# 5_cpu_alu.net
KiCad netlist of a schematic drawn in EAGLE
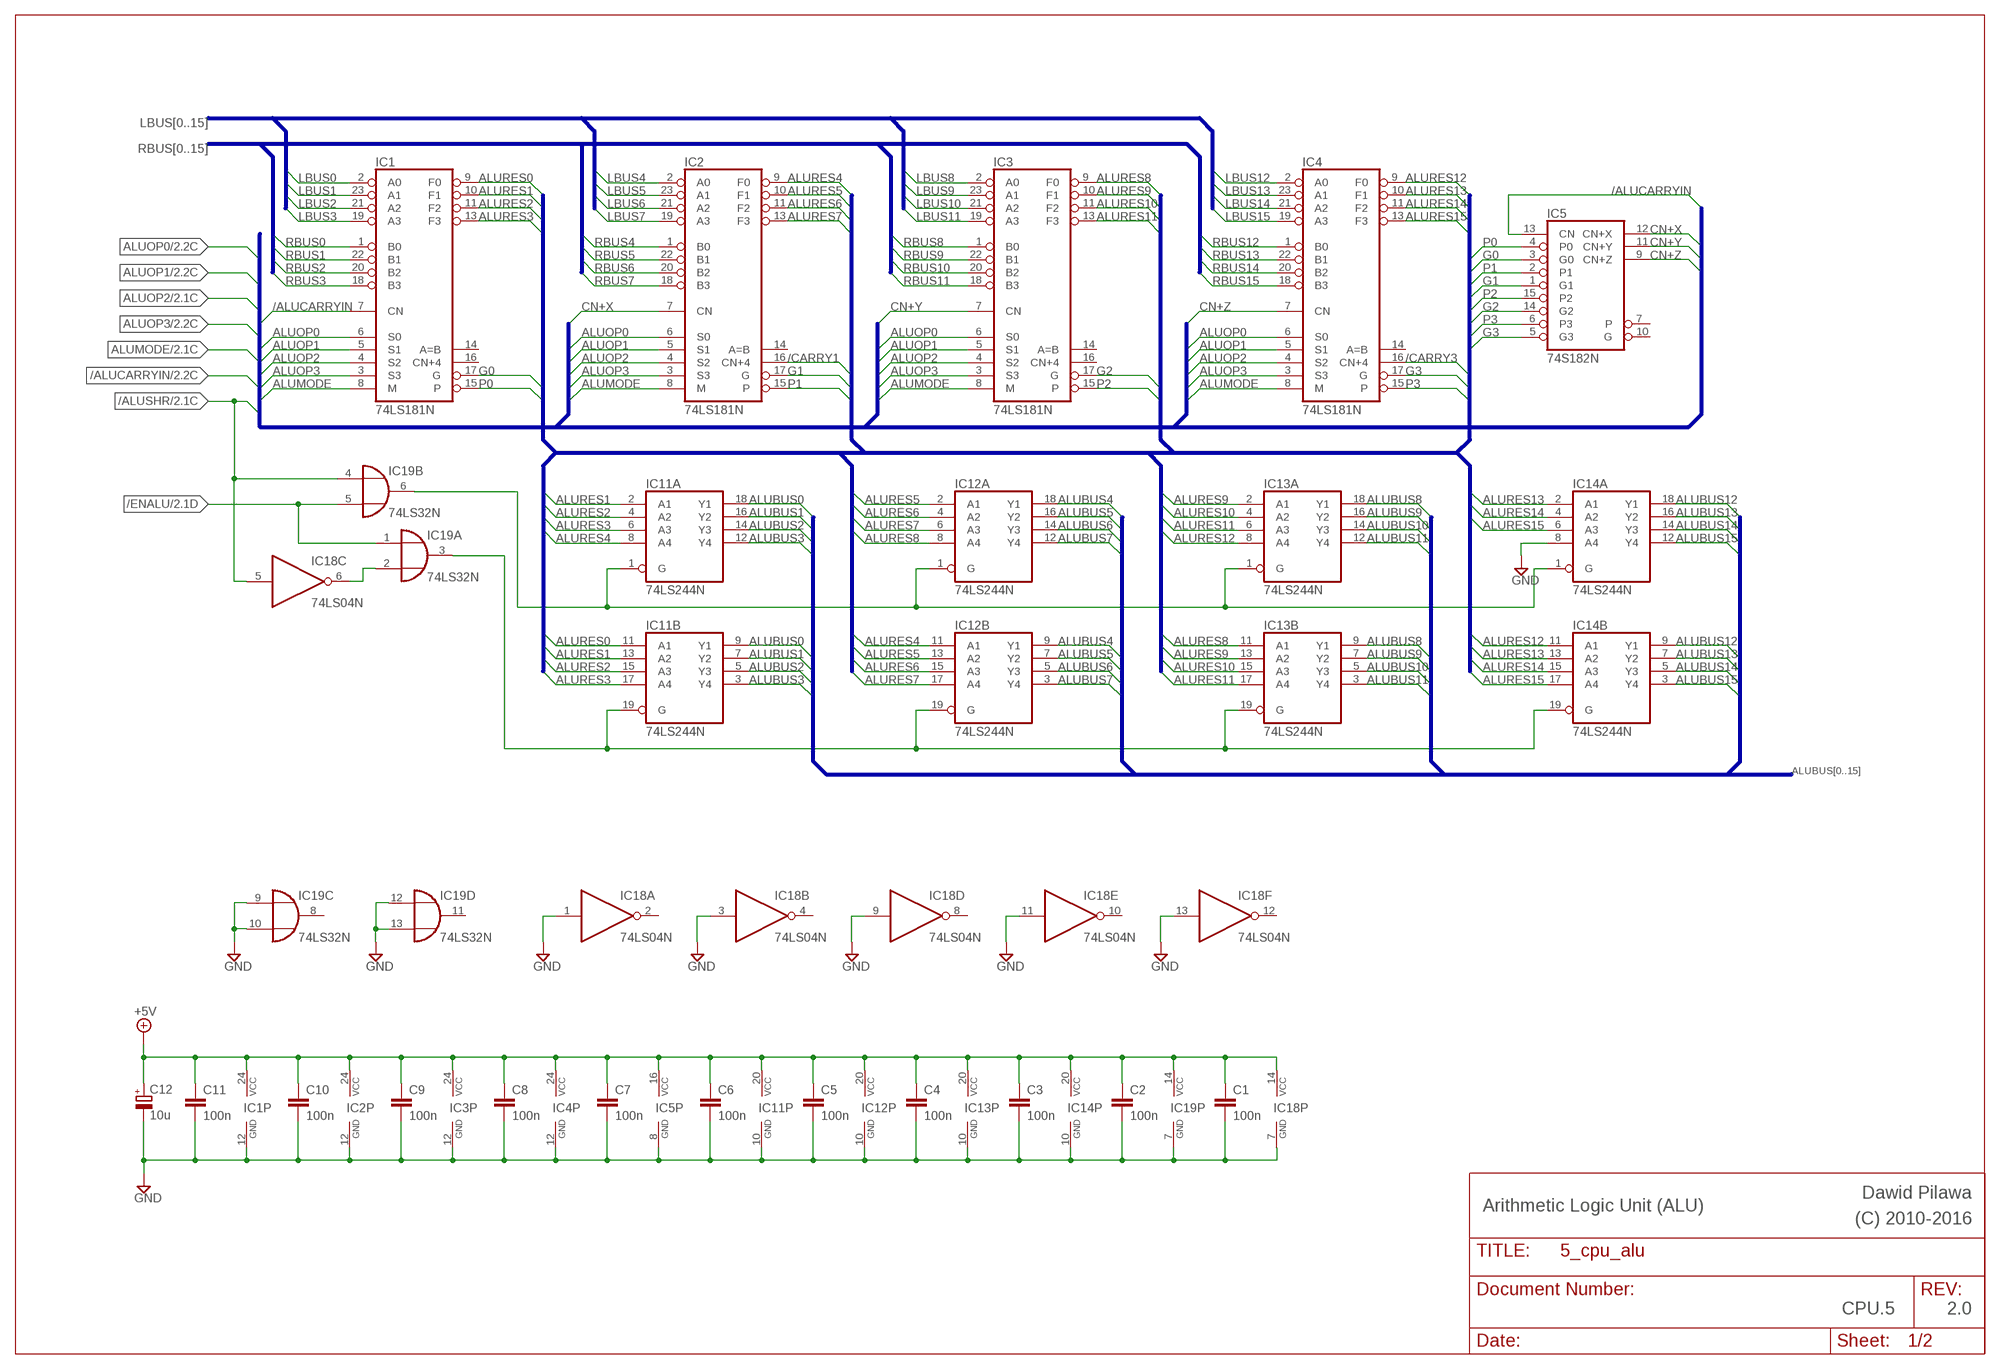
[diagram p0: schematic, sheet 1]
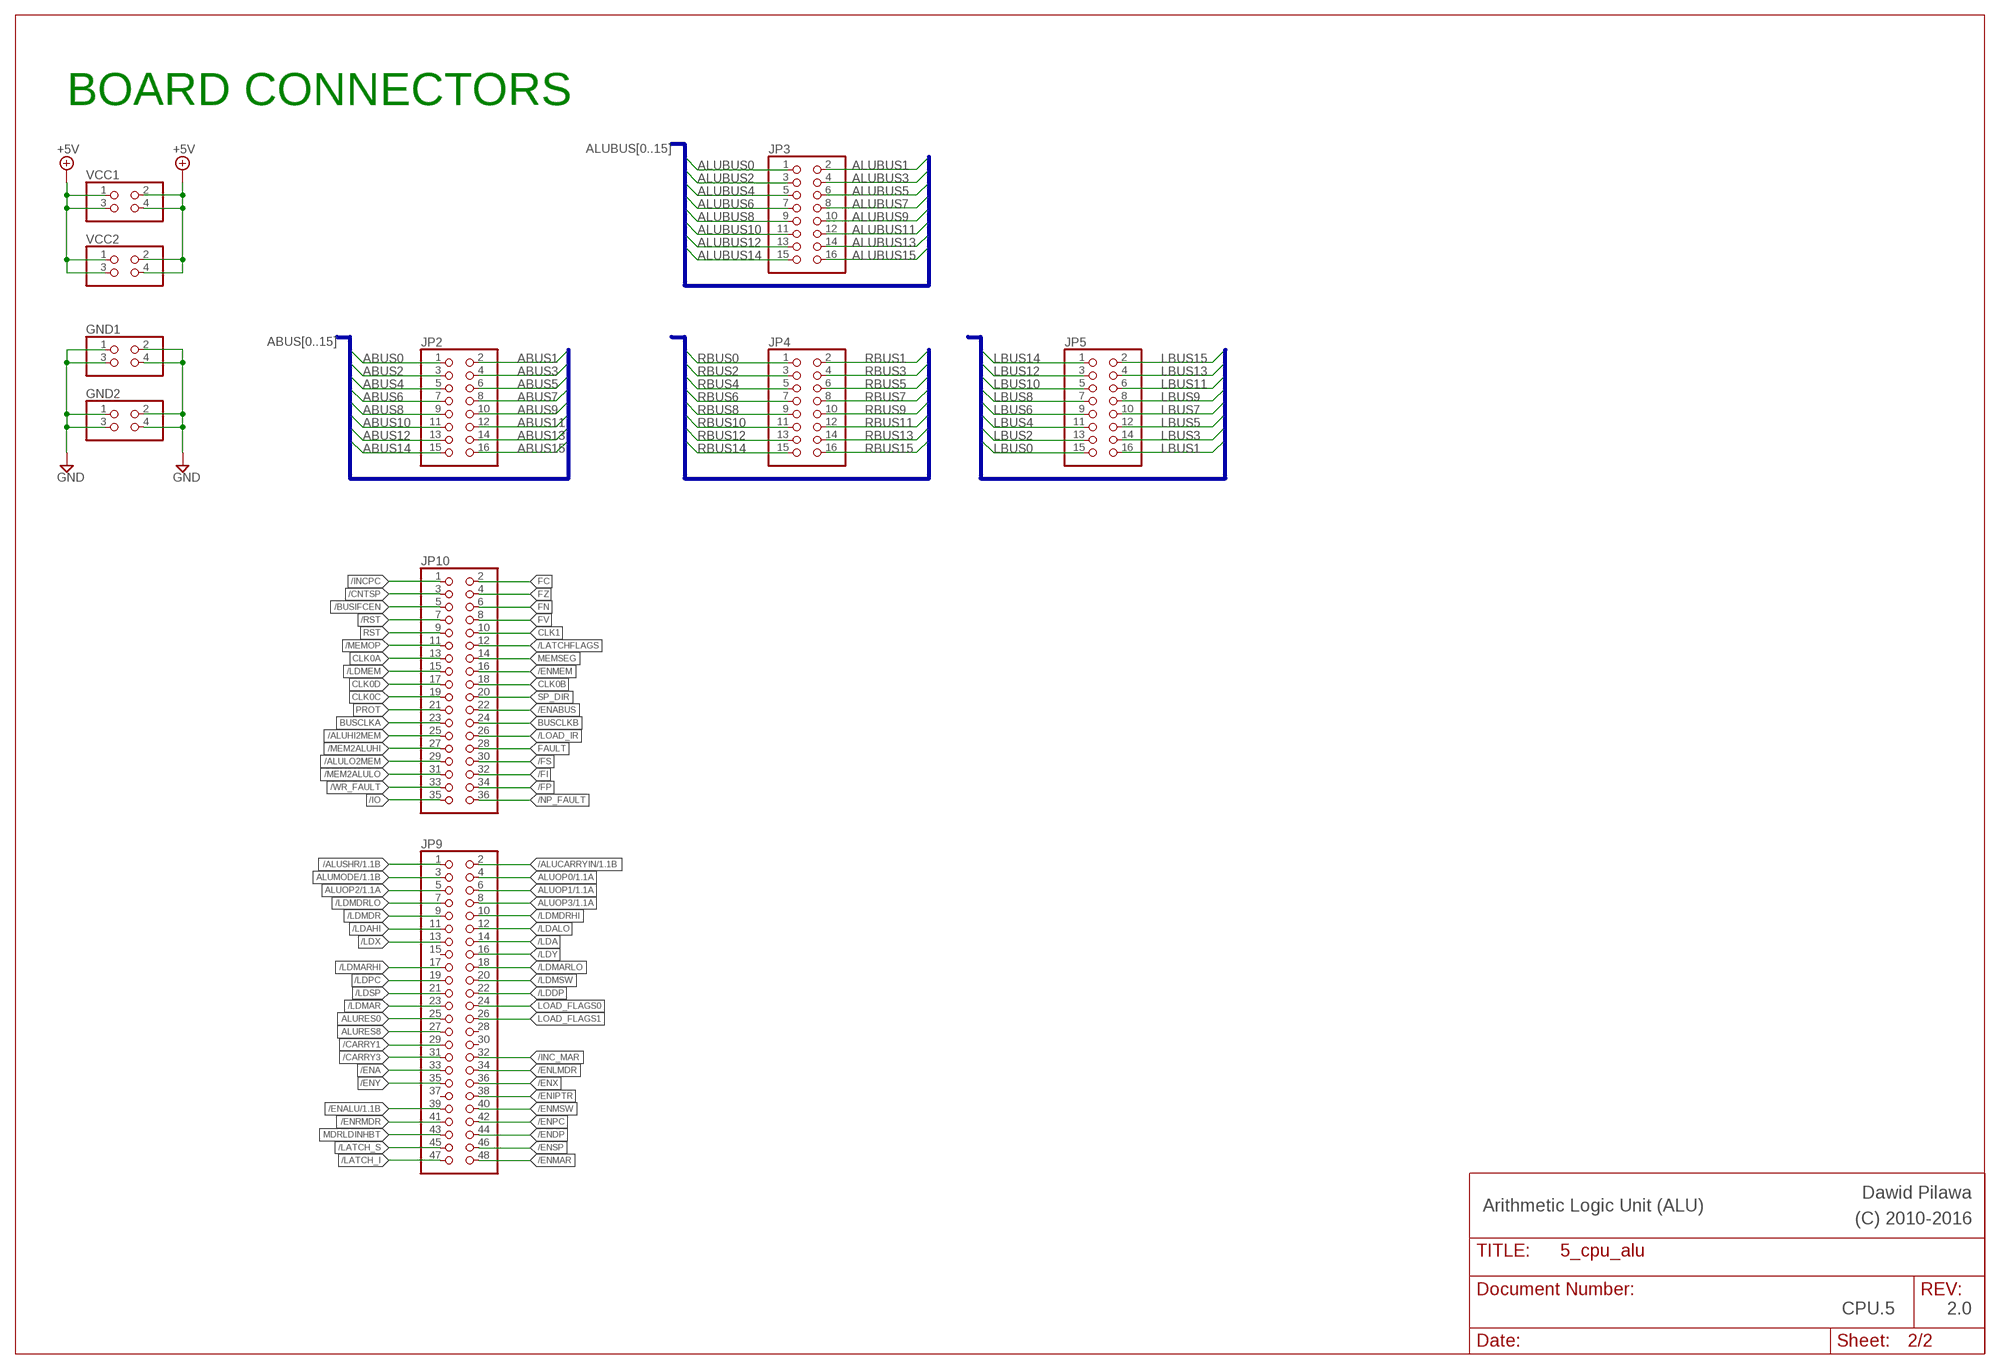
[diagram p1: schematic, sheet 2]

(export (version "E")
  (design (tool "Eeschema 10.0.6"))
  (components
    (comp (ref "C1")
      (value "100n")
      (footprint "eagle-import:C050-024X044")
      (libsource (lib "eagle-import") (part "C-EU050-024X044"))
    )
    (comp (ref "C2")
      (value "100n")
      (footprint "eagle-import:C050-024X044")
      (libsource (lib "eagle-import") (part "C-EU050-024X044"))
    )
    (comp (ref "C3")
      (value "100n")
      (footprint "eagle-import:C050-024X044")
      (libsource (lib "eagle-import") (part "C-EU050-024X044"))
    )
    (comp (ref "C4")
      (value "100n")
      (footprint "eagle-import:C050-024X044")
      (libsource (lib "eagle-import") (part "C-EU050-024X044"))
    )
    (comp (ref "C5")
      (value "100n")
      (footprint "eagle-import:C050-024X044")
      (libsource (lib "eagle-import") (part "C-EU050-024X044"))
    )
    (comp (ref "C6")
      (value "100n")
      (footprint "eagle-import:C050-024X044")
      (libsource (lib "eagle-import") (part "C-EU050-024X044"))
    )
    (comp (ref "C7")
      (value "100n")
      (footprint "eagle-import:C050-024X044")
      (libsource (lib "eagle-import") (part "C-EU050-024X044"))
    )
    (comp (ref "C8")
      (value "100n")
      (footprint "eagle-import:C050-024X044")
      (libsource (lib "eagle-import") (part "C-EU050-024X044"))
    )
    (comp (ref "C9")
      (value "100n")
      (footprint "eagle-import:C050-024X044")
      (libsource (lib "eagle-import") (part "C-EU050-024X044"))
    )
    (comp (ref "C10")
      (value "100n")
      (footprint "eagle-import:C050-024X044")
      (libsource (lib "eagle-import") (part "C-EU050-024X044"))
    )
    (comp (ref "C11")
      (value "100n")
      (footprint "eagle-import:C050-024X044")
      (libsource (lib "eagle-import") (part "C-EU050-024X044"))
    )
    (comp (ref "C12")
      (value "10u")
      (footprint "eagle-import:E2,5-6")
      (libsource (lib "eagle-import") (part "CPOL-EUE2.5-6"))
    )
    (comp (ref "IC1")
      (value "74LS181N")
      (footprint "eagle-import:DIL24-6")
      (libsource (lib "eagle-import") (part "74181NLS"))
    )
    (comp (ref "IC2")
      (value "74LS181N")
      (footprint "eagle-import:DIL24-6")
      (libsource (lib "eagle-import") (part "74181NLS"))
    )
    (comp (ref "IC3")
      (value "74LS181N")
      (footprint "eagle-import:DIL24-6")
      (libsource (lib "eagle-import") (part "74181NLS"))
    )
    (comp (ref "IC4")
      (value "74LS181N")
      (footprint "eagle-import:DIL24-6")
      (libsource (lib "eagle-import") (part "74181NLS"))
    )
    (comp (ref "IC5")
      (value "74S182N")
      (footprint "eagle-import:DIL16")
      (libsource (lib "eagle-import") (part "74182NS"))
    )
    (comp (ref "IC11")
      (value "74LS244N")
      (footprint "eagle-import:DIL20")
      (libsource (lib "eagle-import") (part "74244NLS"))
    )
    (comp (ref "IC12")
      (value "74LS244N")
      (footprint "eagle-import:DIL20")
      (libsource (lib "eagle-import") (part "74244NLS"))
    )
    (comp (ref "IC13")
      (value "74LS244N")
      (footprint "eagle-import:DIL20")
      (libsource (lib "eagle-import") (part "74244NLS"))
    )
    (comp (ref "IC14")
      (value "74LS244N")
      (footprint "eagle-import:DIL20")
      (libsource (lib "eagle-import") (part "74244NLS"))
    )
    (comp (ref "IC18")
      (value "74LS04N")
      (footprint "eagle-import:DIL14")
      (libsource (lib "eagle-import") (part "7404NLS"))
    )
    (comp (ref "IC19")
      (value "74LS32N")
      (footprint "eagle-import:DIL14")
      (libsource (lib "eagle-import") (part "7432NLS"))
    )
    (comp (ref "GND1")
      (value "PINHD-2X2")
      (footprint "eagle-import:2X02")
      (libsource (lib "eagle-import") (part "PINHD-2X2"))
    )
    (comp (ref "GND2")
      (value "PINHD-2X2")
      (footprint "eagle-import:2X02")
      (libsource (lib "eagle-import") (part "PINHD-2X2"))
    )
    (comp (ref "JP2")
      (value "PINHD-2X8")
      (footprint "eagle-import:2X08")
      (libsource (lib "eagle-import") (part "PINHD-2X8"))
    )
    (comp (ref "JP3")
      (value "PINHD-2X8")
      (footprint "eagle-import:2X08")
      (libsource (lib "eagle-import") (part "PINHD-2X8"))
    )
    (comp (ref "JP4")
      (value "PINHD-2X8")
      (footprint "eagle-import:2X08")
      (libsource (lib "eagle-import") (part "PINHD-2X8"))
    )
    (comp (ref "JP5")
      (value "PINHD-2X8")
      (footprint "eagle-import:2X08")
      (libsource (lib "eagle-import") (part "PINHD-2X8"))
    )
    (comp (ref "JP9")
      (value "PINHD-2X24")
      (footprint "eagle-import:2X24")
      (libsource (lib "eagle-import") (part "PINHD-2X24"))
    )
    (comp (ref "JP10")
      (value "PINHD-2X18")
      (footprint "eagle-import:2X18")
      (libsource (lib "eagle-import") (part "PINHD-2X18"))
    )
    (comp (ref "VCC1")
      (value "PINHD-2X2")
      (footprint "eagle-import:2X02")
      (libsource (lib "eagle-import") (part "PINHD-2X2"))
    )
    (comp (ref "VCC2")
      (value "PINHD-2X2")
      (footprint "eagle-import:2X02")
      (libsource (lib "eagle-import") (part "PINHD-2X2"))
    )
  )
  (nets
    (net (code "1") (name "+5V") (class "Default")
      (node (ref "C1") (pin "1") (pinfunction "1_1") (pintype "passive"))
      (node (ref "C10") (pin "1") (pinfunction "1_1") (pintype "passive"))
      (node (ref "C11") (pin "1") (pinfunction "1_1") (pintype "passive"))
      (node (ref "C12") (pin "+") (pinfunction "+_+") (pintype "passive"))
      (node (ref "C2") (pin "1") (pinfunction "1_1") (pintype "passive"))
      (node (ref "C3") (pin "1") (pinfunction "1_1") (pintype "passive"))
      (node (ref "C4") (pin "1") (pinfunction "1_1") (pintype "passive"))
      (node (ref "C5") (pin "1") (pinfunction "1_1") (pintype "passive"))
      (node (ref "C6") (pin "1") (pinfunction "1_1") (pintype "passive"))
      (node (ref "C7") (pin "1") (pinfunction "1_1") (pintype "passive"))
      (node (ref "C8") (pin "1") (pinfunction "1_1") (pintype "passive"))
      (node (ref "C9") (pin "1") (pinfunction "1_1") (pintype "passive"))
      (node (ref "IC1") (pin "24") (pinfunction "VCC_24") (pintype "power_in"))
      (node (ref "IC11") (pin "20") (pinfunction "VCC_20") (pintype "power_in"))
      (node (ref "IC12") (pin "20") (pinfunction "VCC_20") (pintype "power_in"))
      (node (ref "IC13") (pin "20") (pinfunction "VCC_20") (pintype "power_in"))
      (node (ref "IC14") (pin "20") (pinfunction "VCC_20") (pintype "power_in"))
      (node (ref "IC18") (pin "14") (pinfunction "VCC_14") (pintype "power_in"))
      (node (ref "IC19") (pin "14") (pinfunction "VCC_14") (pintype "power_in"))
      (node (ref "IC2") (pin "24") (pinfunction "VCC_24") (pintype "power_in"))
      (node (ref "IC3") (pin "24") (pinfunction "VCC_24") (pintype "power_in"))
      (node (ref "IC4") (pin "24") (pinfunction "VCC_24") (pintype "power_in"))
      (node (ref "IC5") (pin "16") (pinfunction "VCC_16") (pintype "power_in"))
      (node (ref "VCC1") (pin "1") (pinfunction "1_1") (pintype "passive"))
      (node (ref "VCC1") (pin "2") (pinfunction "2_2") (pintype "passive"))
      (node (ref "VCC1") (pin "3") (pinfunction "3_3") (pintype "passive"))
      (node (ref "VCC1") (pin "4") (pinfunction "4_4") (pintype "passive"))
      (node (ref "VCC2") (pin "1") (pinfunction "1_1") (pintype "passive"))
      (node (ref "VCC2") (pin "2") (pinfunction "2_2") (pintype "passive"))
      (node (ref "VCC2") (pin "3") (pinfunction "3_3") (pintype "passive"))
      (node (ref "VCC2") (pin "4") (pinfunction "4_4") (pintype "passive"))
    )
    (net (code "8") (name "ABUS0") (class "Default")
      (node (ref "JP2") (pin "1") (pinfunction "1_1") (pintype "passive"))
    )
    (net (code "9") (name "ABUS1") (class "Default")
      (node (ref "JP2") (pin "2") (pinfunction "2_2") (pintype "passive"))
    )
    (net (code "10") (name "ABUS2") (class "Default")
      (node (ref "JP2") (pin "3") (pinfunction "3_3") (pintype "passive"))
    )
    (net (code "11") (name "ABUS3") (class "Default")
      (node (ref "JP2") (pin "4") (pinfunction "4_4") (pintype "passive"))
    )
    (net (code "12") (name "ABUS4") (class "Default")
      (node (ref "JP2") (pin "5") (pinfunction "5_5") (pintype "passive"))
    )
    (net (code "13") (name "ABUS5") (class "Default")
      (node (ref "JP2") (pin "6") (pinfunction "6_6") (pintype "passive"))
    )
    (net (code "14") (name "ABUS6") (class "Default")
      (node (ref "JP2") (pin "7") (pinfunction "7_7") (pintype "passive"))
    )
    (net (code "15") (name "ABUS7") (class "Default")
      (node (ref "JP2") (pin "8") (pinfunction "8_8") (pintype "passive"))
    )
    (net (code "16") (name "ABUS8") (class "Default")
      (node (ref "JP2") (pin "9") (pinfunction "9_9") (pintype "passive"))
    )
    (net (code "17") (name "ABUS9") (class "Default")
      (node (ref "JP2") (pin "10") (pinfunction "10_10") (pintype "passive"))
    )
    (net (code "18") (name "ABUS10") (class "Default")
      (node (ref "JP2") (pin "11") (pinfunction "11_11") (pintype "passive"))
    )
    (net (code "19") (name "ABUS11") (class "Default")
      (node (ref "JP2") (pin "12") (pinfunction "12_12") (pintype "passive"))
    )
    (net (code "20") (name "ABUS12") (class "Default")
      (node (ref "JP2") (pin "13") (pinfunction "13_13") (pintype "passive"))
    )
    (net (code "21") (name "ABUS13") (class "Default")
      (node (ref "JP2") (pin "14") (pinfunction "14_14") (pintype "passive"))
    )
    (net (code "22") (name "ABUS14") (class "Default")
      (node (ref "JP2") (pin "15") (pinfunction "15_15") (pintype "passive"))
    )
    (net (code "23") (name "ABUS15") (class "Default")
      (node (ref "JP2") (pin "16") (pinfunction "16_16") (pintype "passive"))
    )
    (net (code "24") (name "ALUBUS0") (class "Default")
      (node (ref "IC11") (pin "18") (pinfunction "Y1_18") (pintype "tri_state"))
      (node (ref "IC11") (pin "9") (pinfunction "Y1_9") (pintype "tri_state"))
      (node (ref "JP3") (pin "1") (pinfunction "1_1") (pintype "passive"))
    )
    (net (code "25") (name "ALUBUS1") (class "Default")
      (node (ref "IC11") (pin "16") (pinfunction "Y2_16") (pintype "tri_state"))
      (node (ref "IC11") (pin "7") (pinfunction "Y2_7") (pintype "tri_state"))
      (node (ref "JP3") (pin "2") (pinfunction "2_2") (pintype "passive"))
    )
    (net (code "26") (name "ALUBUS2") (class "Default")
      (node (ref "IC11") (pin "14") (pinfunction "Y3_14") (pintype "tri_state"))
      (node (ref "IC11") (pin "5") (pinfunction "Y3_5") (pintype "tri_state"))
      (node (ref "JP3") (pin "3") (pinfunction "3_3") (pintype "passive"))
    )
    (net (code "27") (name "ALUBUS3") (class "Default")
      (node (ref "IC11") (pin "12") (pinfunction "Y4_12") (pintype "tri_state"))
      (node (ref "IC11") (pin "3") (pinfunction "Y4_3") (pintype "tri_state"))
      (node (ref "JP3") (pin "4") (pinfunction "4_4") (pintype "passive"))
    )
    (net (code "28") (name "ALUBUS4") (class "Default")
      (node (ref "IC12") (pin "18") (pinfunction "Y1_18") (pintype "tri_state"))
      (node (ref "IC12") (pin "9") (pinfunction "Y1_9") (pintype "tri_state"))
      (node (ref "JP3") (pin "5") (pinfunction "5_5") (pintype "passive"))
    )
    (net (code "29") (name "ALUBUS5") (class "Default")
      (node (ref "IC12") (pin "16") (pinfunction "Y2_16") (pintype "tri_state"))
      (node (ref "IC12") (pin "7") (pinfunction "Y2_7") (pintype "tri_state"))
      (node (ref "JP3") (pin "6") (pinfunction "6_6") (pintype "passive"))
    )
    (net (code "30") (name "ALUBUS6") (class "Default")
      (node (ref "IC12") (pin "14") (pinfunction "Y3_14") (pintype "tri_state"))
      (node (ref "IC12") (pin "5") (pinfunction "Y3_5") (pintype "tri_state"))
      (node (ref "JP3") (pin "7") (pinfunction "7_7") (pintype "passive"))
    )
    (net (code "31") (name "ALUBUS7") (class "Default")
      (node (ref "IC12") (pin "12") (pinfunction "Y4_12") (pintype "tri_state"))
      (node (ref "IC12") (pin "3") (pinfunction "Y4_3") (pintype "tri_state"))
      (node (ref "JP3") (pin "8") (pinfunction "8_8") (pintype "passive"))
    )
    (net (code "32") (name "ALUBUS8") (class "Default")
      (node (ref "IC13") (pin "18") (pinfunction "Y1_18") (pintype "tri_state"))
      (node (ref "IC13") (pin "9") (pinfunction "Y1_9") (pintype "tri_state"))
      (node (ref "JP3") (pin "9") (pinfunction "9_9") (pintype "passive"))
    )
    (net (code "33") (name "ALUBUS9") (class "Default")
      (node (ref "IC13") (pin "16") (pinfunction "Y2_16") (pintype "tri_state"))
      (node (ref "IC13") (pin "7") (pinfunction "Y2_7") (pintype "tri_state"))
      (node (ref "JP3") (pin "10") (pinfunction "10_10") (pintype "passive"))
    )
    (net (code "34") (name "ALUBUS10") (class "Default")
      (node (ref "IC13") (pin "14") (pinfunction "Y3_14") (pintype "tri_state"))
      (node (ref "IC13") (pin "5") (pinfunction "Y3_5") (pintype "tri_state"))
      (node (ref "JP3") (pin "11") (pinfunction "11_11") (pintype "passive"))
    )
    (net (code "35") (name "ALUBUS11") (class "Default")
      (node (ref "IC13") (pin "12") (pinfunction "Y4_12") (pintype "tri_state"))
      (node (ref "IC13") (pin "3") (pinfunction "Y4_3") (pintype "tri_state"))
      (node (ref "JP3") (pin "12") (pinfunction "12_12") (pintype "passive"))
    )
    (net (code "36") (name "ALUBUS12") (class "Default")
      (node (ref "IC14") (pin "18") (pinfunction "Y1_18") (pintype "tri_state"))
      (node (ref "IC14") (pin "9") (pinfunction "Y1_9") (pintype "tri_state"))
      (node (ref "JP3") (pin "13") (pinfunction "13_13") (pintype "passive"))
    )
    (net (code "37") (name "ALUBUS13") (class "Default")
      (node (ref "IC14") (pin "16") (pinfunction "Y2_16") (pintype "tri_state"))
      (node (ref "IC14") (pin "7") (pinfunction "Y2_7") (pintype "tri_state"))
      (node (ref "JP3") (pin "14") (pinfunction "14_14") (pintype "passive"))
    )
    (net (code "38") (name "ALUBUS14") (class "Default")
      (node (ref "IC14") (pin "14") (pinfunction "Y3_14") (pintype "tri_state"))
      (node (ref "IC14") (pin "5") (pinfunction "Y3_5") (pintype "tri_state"))
      (node (ref "JP3") (pin "15") (pinfunction "15_15") (pintype "passive"))
    )
    (net (code "39") (name "ALUBUS15") (class "Default")
      (node (ref "IC14") (pin "12") (pinfunction "Y4_12") (pintype "tri_state"))
      (node (ref "IC14") (pin "3") (pinfunction "Y4_3") (pintype "tri_state"))
      (node (ref "JP3") (pin "16") (pinfunction "16_16") (pintype "passive"))
    )
    (net (code "40") (name "ALUMODE") (class "Default")
      (node (ref "IC1") (pin "8") (pinfunction "M_8") (pintype "input"))
      (node (ref "IC2") (pin "8") (pinfunction "M_8") (pintype "input"))
      (node (ref "IC3") (pin "8") (pinfunction "M_8") (pintype "input"))
      (node (ref "IC4") (pin "8") (pinfunction "M_8") (pintype "input"))
      (node (ref "JP9") (pin "3") (pinfunction "3_3") (pintype "passive"))
    )
    (net (code "41") (name "ALUOP0") (class "Default")
      (node (ref "IC1") (pin "6") (pinfunction "S0_6") (pintype "input"))
      (node (ref "IC2") (pin "6") (pinfunction "S0_6") (pintype "input"))
      (node (ref "IC3") (pin "6") (pinfunction "S0_6") (pintype "input"))
      (node (ref "IC4") (pin "6") (pinfunction "S0_6") (pintype "input"))
      (node (ref "JP9") (pin "4") (pinfunction "4_4") (pintype "passive"))
    )
    (net (code "42") (name "ALUOP1") (class "Default")
      (node (ref "IC1") (pin "5") (pinfunction "S1_5") (pintype "input"))
      (node (ref "IC2") (pin "5") (pinfunction "S1_5") (pintype "input"))
      (node (ref "IC3") (pin "5") (pinfunction "S1_5") (pintype "input"))
      (node (ref "IC4") (pin "5") (pinfunction "S1_5") (pintype "input"))
      (node (ref "JP9") (pin "6") (pinfunction "6_6") (pintype "passive"))
    )
    (net (code "43") (name "ALUOP2") (class "Default")
      (node (ref "IC1") (pin "4") (pinfunction "S2_4") (pintype "input"))
      (node (ref "IC2") (pin "4") (pinfunction "S2_4") (pintype "input"))
      (node (ref "IC3") (pin "4") (pinfunction "S2_4") (pintype "input"))
      (node (ref "IC4") (pin "4") (pinfunction "S2_4") (pintype "input"))
      (node (ref "JP9") (pin "5") (pinfunction "5_5") (pintype "passive"))
    )
    (net (code "44") (name "ALUOP3") (class "Default")
      (node (ref "IC1") (pin "3") (pinfunction "S3_3") (pintype "input"))
      (node (ref "IC2") (pin "3") (pinfunction "S3_3") (pintype "input"))
      (node (ref "IC3") (pin "3") (pinfunction "S3_3") (pintype "input"))
      (node (ref "IC4") (pin "3") (pinfunction "S3_3") (pintype "input"))
      (node (ref "JP9") (pin "8") (pinfunction "8_8") (pintype "passive"))
    )
    (net (code "45") (name "ALURES0") (class "Default")
      (node (ref "IC1") (pin "9") (pinfunction "F0_9") (pintype "output"))
      (node (ref "IC11") (pin "11") (pinfunction "A1_11") (pintype "input"))
      (node (ref "JP9") (pin "25") (pinfunction "25_25") (pintype "passive"))
    )
    (net (code "46") (name "ALURES1") (class "Default")
      (node (ref "IC1") (pin "10") (pinfunction "F1_10") (pintype "output"))
      (node (ref "IC11") (pin "13") (pinfunction "A2_13") (pintype "input"))
      (node (ref "IC11") (pin "2") (pinfunction "A1_2") (pintype "input"))
    )
    (net (code "47") (name "ALURES2") (class "Default")
      (node (ref "IC1") (pin "11") (pinfunction "F2_11") (pintype "output"))
      (node (ref "IC11") (pin "15") (pinfunction "A3_15") (pintype "input"))
      (node (ref "IC11") (pin "4") (pinfunction "A2_4") (pintype "input"))
    )
    (net (code "48") (name "ALURES3") (class "Default")
      (node (ref "IC1") (pin "13") (pinfunction "F3_13") (pintype "output"))
      (node (ref "IC11") (pin "17") (pinfunction "A4_17") (pintype "input"))
      (node (ref "IC11") (pin "6") (pinfunction "A3_6") (pintype "input"))
    )
    (net (code "49") (name "ALURES4") (class "Default")
      (node (ref "IC11") (pin "8") (pinfunction "A4_8") (pintype "input"))
      (node (ref "IC12") (pin "11") (pinfunction "A1_11") (pintype "input"))
      (node (ref "IC2") (pin "9") (pinfunction "F0_9") (pintype "output"))
    )
    (net (code "50") (name "ALURES5") (class "Default")
      (node (ref "IC12") (pin "13") (pinfunction "A2_13") (pintype "input"))
      (node (ref "IC12") (pin "2") (pinfunction "A1_2") (pintype "input"))
      (node (ref "IC2") (pin "10") (pinfunction "F1_10") (pintype "output"))
    )
    (net (code "51") (name "ALURES6") (class "Default")
      (node (ref "IC12") (pin "15") (pinfunction "A3_15") (pintype "input"))
      (node (ref "IC12") (pin "4") (pinfunction "A2_4") (pintype "input"))
      (node (ref "IC2") (pin "11") (pinfunction "F2_11") (pintype "output"))
    )
    (net (code "52") (name "ALURES7") (class "Default")
      (node (ref "IC12") (pin "17") (pinfunction "A4_17") (pintype "input"))
      (node (ref "IC12") (pin "6") (pinfunction "A3_6") (pintype "input"))
      (node (ref "IC2") (pin "13") (pinfunction "F3_13") (pintype "output"))
    )
    (net (code "53") (name "ALURES8") (class "Default")
      (node (ref "IC12") (pin "8") (pinfunction "A4_8") (pintype "input"))
      (node (ref "IC13") (pin "11") (pinfunction "A1_11") (pintype "input"))
      (node (ref "IC3") (pin "9") (pinfunction "F0_9") (pintype "output"))
      (node (ref "JP9") (pin "27") (pinfunction "27_27") (pintype "passive"))
    )
    (net (code "54") (name "ALURES9") (class "Default")
      (node (ref "IC13") (pin "13") (pinfunction "A2_13") (pintype "input"))
      (node (ref "IC13") (pin "2") (pinfunction "A1_2") (pintype "input"))
      (node (ref "IC3") (pin "10") (pinfunction "F1_10") (pintype "output"))
    )
    (net (code "55") (name "ALURES10") (class "Default")
      (node (ref "IC13") (pin "15") (pinfunction "A3_15") (pintype "input"))
      (node (ref "IC13") (pin "4") (pinfunction "A2_4") (pintype "input"))
      (node (ref "IC3") (pin "11") (pinfunction "F2_11") (pintype "output"))
    )
    (net (code "56") (name "ALURES11") (class "Default")
      (node (ref "IC13") (pin "17") (pinfunction "A4_17") (pintype "input"))
      (node (ref "IC13") (pin "6") (pinfunction "A3_6") (pintype "input"))
      (node (ref "IC3") (pin "13") (pinfunction "F3_13") (pintype "output"))
    )
    (net (code "57") (name "ALURES12") (class "Default")
      (node (ref "IC13") (pin "8") (pinfunction "A4_8") (pintype "input"))
      (node (ref "IC14") (pin "11") (pinfunction "A1_11") (pintype "input"))
      (node (ref "IC4") (pin "9") (pinfunction "F0_9") (pintype "output"))
    )
    (net (code "58") (name "ALURES13") (class "Default")
      (node (ref "IC14") (pin "13") (pinfunction "A2_13") (pintype "input"))
      (node (ref "IC14") (pin "2") (pinfunction "A1_2") (pintype "input"))
      (node (ref "IC4") (pin "10") (pinfunction "F1_10") (pintype "output"))
    )
    (net (code "59") (name "ALURES14") (class "Default")
      (node (ref "IC14") (pin "15") (pinfunction "A3_15") (pintype "input"))
      (node (ref "IC14") (pin "4") (pinfunction "A2_4") (pintype "input"))
      (node (ref "IC4") (pin "11") (pinfunction "F2_11") (pintype "output"))
    )
    (net (code "60") (name "ALURES15") (class "Default")
      (node (ref "IC14") (pin "17") (pinfunction "A4_17") (pintype "input"))
      (node (ref "IC14") (pin "6") (pinfunction "A3_6") (pintype "input"))
      (node (ref "IC4") (pin "13") (pinfunction "F3_13") (pintype "output"))
    )
    (net (code "61") (name "BUSCLKA") (class "Default")
      (node (ref "JP10") (pin "23") (pinfunction "23_23") (pintype "passive"))
    )
    (net (code "62") (name "BUSCLKB") (class "Default")
      (node (ref "JP10") (pin "24") (pinfunction "24_24") (pintype "passive"))
    )
    (net (code "63") (name "CLK0A") (class "Default")
      (node (ref "JP10") (pin "13") (pinfunction "13_13") (pintype "passive"))
    )
    (net (code "64") (name "CLK0B") (class "Default")
      (node (ref "JP10") (pin "18") (pinfunction "18_18") (pintype "passive"))
    )
    (net (code "65") (name "CLK0C") (class "Default")
      (node (ref "JP10") (pin "19") (pinfunction "19_19") (pintype "passive"))
    )
    (net (code "66") (name "CLK0D") (class "Default")
      (node (ref "JP10") (pin "17") (pinfunction "17_17") (pintype "passive"))
    )
    (net (code "67") (name "CLK1") (class "Default")
      (node (ref "JP10") (pin "10") (pinfunction "10_10") (pintype "passive"))
    )
    (net (code "68") (name "CN+X") (class "Default")
      (node (ref "IC2") (pin "7") (pinfunction "CN_7") (pintype "input"))
      (node (ref "IC5") (pin "12") (pinfunction "CN+X_12") (pintype "output"))
    )
    (net (code "69") (name "CN+Y") (class "Default")
      (node (ref "IC3") (pin "7") (pinfunction "CN_7") (pintype "input"))
      (node (ref "IC5") (pin "11") (pinfunction "CN+Y_11") (pintype "output"))
    )
    (net (code "70") (name "CN+Z") (class "Default")
      (node (ref "IC4") (pin "7") (pinfunction "CN_7") (pintype "input"))
      (node (ref "IC5") (pin "9") (pinfunction "CN+Z_9") (pintype "output"))
    )
    (net (code "71") (name "FAULT") (class "Default")
      (node (ref "JP10") (pin "28") (pinfunction "28_28") (pintype "passive"))
    )
    (net (code "72") (name "FC") (class "Default")
      (node (ref "JP10") (pin "2") (pinfunction "2_2") (pintype "passive"))
    )
    (net (code "73") (name "FN") (class "Default")
      (node (ref "JP10") (pin "6") (pinfunction "6_6") (pintype "passive"))
    )
    (net (code "74") (name "FV") (class "Default")
      (node (ref "JP10") (pin "8") (pinfunction "8_8") (pintype "passive"))
    )
    (net (code "75") (name "FZ") (class "Default")
      (node (ref "JP10") (pin "4") (pinfunction "4_4") (pintype "passive"))
    )
    (net (code "76") (name "G0") (class "Default")
      (node (ref "IC1") (pin "17") (pinfunction "G_17") (pintype "output"))
      (node (ref "IC5") (pin "3") (pinfunction "G0_3") (pintype "input"))
    )
    (net (code "77") (name "G1") (class "Default")
      (node (ref "IC2") (pin "17") (pinfunction "G_17") (pintype "output"))
      (node (ref "IC5") (pin "1") (pinfunction "G1_1") (pintype "input"))
    )
    (net (code "78") (name "G2") (class "Default")
      (node (ref "IC3") (pin "17") (pinfunction "G_17") (pintype "output"))
      (node (ref "IC5") (pin "14") (pinfunction "G2_14") (pintype "input"))
    )
    (net (code "79") (name "G3") (class "Default")
      (node (ref "IC4") (pin "17") (pinfunction "G_17") (pintype "output"))
      (node (ref "IC5") (pin "5") (pinfunction "G3_5") (pintype "input"))
    )
    (net (code "80") (name "GND") (class "Default")
      (node (ref "C1") (pin "2") (pinfunction "2_2") (pintype "passive"))
      (node (ref "C10") (pin "2") (pinfunction "2_2") (pintype "passive"))
      (node (ref "C11") (pin "2") (pinfunction "2_2") (pintype "passive"))
      (node (ref "C12") (pin "-") (pinfunction "-_-") (pintype "passive"))
      (node (ref "C2") (pin "2") (pinfunction "2_2") (pintype "passive"))
      (node (ref "C3") (pin "2") (pinfunction "2_2") (pintype "passive"))
      (node (ref "C4") (pin "2") (pinfunction "2_2") (pintype "passive"))
      (node (ref "C5") (pin "2") (pinfunction "2_2") (pintype "passive"))
      (node (ref "C6") (pin "2") (pinfunction "2_2") (pintype "passive"))
      (node (ref "C7") (pin "2") (pinfunction "2_2") (pintype "passive"))
      (node (ref "C8") (pin "2") (pinfunction "2_2") (pintype "passive"))
      (node (ref "C9") (pin "2") (pinfunction "2_2") (pintype "passive"))
      (node (ref "GND1") (pin "1") (pinfunction "1_1") (pintype "passive"))
      (node (ref "GND1") (pin "2") (pinfunction "2_2") (pintype "passive"))
      (node (ref "GND1") (pin "3") (pinfunction "3_3") (pintype "passive"))
      (node (ref "GND1") (pin "4") (pinfunction "4_4") (pintype "passive"))
      (node (ref "GND2") (pin "1") (pinfunction "1_1") (pintype "passive"))
      (node (ref "GND2") (pin "2") (pinfunction "2_2") (pintype "passive"))
      (node (ref "GND2") (pin "3") (pinfunction "3_3") (pintype "passive"))
      (node (ref "GND2") (pin "4") (pinfunction "4_4") (pintype "passive"))
      (node (ref "IC1") (pin "12") (pinfunction "GND_12") (pintype "power_in"))
      (node (ref "IC11") (pin "10") (pinfunction "GND_10") (pintype "power_in"))
      (node (ref "IC12") (pin "10") (pinfunction "GND_10") (pintype "power_in"))
      (node (ref "IC13") (pin "10") (pinfunction "GND_10") (pintype "power_in"))
      (node (ref "IC14") (pin "10") (pinfunction "GND_10") (pintype "power_in"))
      (node (ref "IC14") (pin "8") (pinfunction "A4_8") (pintype "input"))
      (node (ref "IC18") (pin "1") (pinfunction "I_1") (pintype "input"))
      (node (ref "IC18") (pin "11") (pinfunction "I_11") (pintype "input"))
      (node (ref "IC18") (pin "13") (pinfunction "I_13") (pintype "input"))
      (node (ref "IC18") (pin "3") (pinfunction "I_3") (pintype "input"))
      (node (ref "IC18") (pin "7") (pinfunction "GND_7") (pintype "power_in"))
      (node (ref "IC18") (pin "9") (pinfunction "I_9") (pintype "input"))
      (node (ref "IC19") (pin "10") (pinfunction "I1_10") (pintype "input"))
      (node (ref "IC19") (pin "12") (pinfunction "I0_12") (pintype "input"))
      (node (ref "IC19") (pin "13") (pinfunction "I1_13") (pintype "input"))
      (node (ref "IC19") (pin "7") (pinfunction "GND_7") (pintype "power_in"))
      (node (ref "IC19") (pin "9") (pinfunction "I0_9") (pintype "input"))
      (node (ref "IC2") (pin "12") (pinfunction "GND_12") (pintype "power_in"))
      (node (ref "IC3") (pin "12") (pinfunction "GND_12") (pintype "power_in"))
      (node (ref "IC4") (pin "12") (pinfunction "GND_12") (pintype "power_in"))
      (node (ref "IC5") (pin "8") (pinfunction "GND_8") (pintype "power_in"))
    )
    (net (code "81") (name "LBUS0") (class "Default")
      (node (ref "IC1") (pin "2") (pinfunction "A0_2") (pintype "input"))
      (node (ref "JP5") (pin "15") (pinfunction "15_15") (pintype "passive"))
    )
    (net (code "82") (name "LBUS1") (class "Default")
      (node (ref "IC1") (pin "23") (pinfunction "A1_23") (pintype "input"))
      (node (ref "JP5") (pin "16") (pinfunction "16_16") (pintype "passive"))
    )
    (net (code "83") (name "LBUS2") (class "Default")
      (node (ref "IC1") (pin "21") (pinfunction "A2_21") (pintype "input"))
      (node (ref "JP5") (pin "13") (pinfunction "13_13") (pintype "passive"))
    )
    (net (code "84") (name "LBUS3") (class "Default")
      (node (ref "IC1") (pin "19") (pinfunction "A3_19") (pintype "input"))
      (node (ref "JP5") (pin "14") (pinfunction "14_14") (pintype "passive"))
    )
    (net (code "85") (name "LBUS4") (class "Default")
      (node (ref "IC2") (pin "2") (pinfunction "A0_2") (pintype "input"))
      (node (ref "JP5") (pin "11") (pinfunction "11_11") (pintype "passive"))
    )
    (net (code "86") (name "LBUS5") (class "Default")
      (node (ref "IC2") (pin "23") (pinfunction "A1_23") (pintype "input"))
      (node (ref "JP5") (pin "12") (pinfunction "12_12") (pintype "passive"))
    )
    (net (code "87") (name "LBUS6") (class "Default")
      (node (ref "IC2") (pin "21") (pinfunction "A2_21") (pintype "input"))
      (node (ref "JP5") (pin "9") (pinfunction "9_9") (pintype "passive"))
    )
    (net (code "88") (name "LBUS7") (class "Default")
      (node (ref "IC2") (pin "19") (pinfunction "A3_19") (pintype "input"))
      (node (ref "JP5") (pin "10") (pinfunction "10_10") (pintype "passive"))
    )
    (net (code "89") (name "LBUS8") (class "Default")
      (node (ref "IC3") (pin "2") (pinfunction "A0_2") (pintype "input"))
      (node (ref "JP5") (pin "7") (pinfunction "7_7") (pintype "passive"))
    )
    (net (code "90") (name "LBUS9") (class "Default")
      (node (ref "IC3") (pin "23") (pinfunction "A1_23") (pintype "input"))
      (node (ref "JP5") (pin "8") (pinfunction "8_8") (pintype "passive"))
    )
    (net (code "91") (name "LBUS10") (class "Default")
      (node (ref "IC3") (pin "21") (pinfunction "A2_21") (pintype "input"))
      (node (ref "JP5") (pin "5") (pinfunction "5_5") (pintype "passive"))
    )
    (net (code "92") (name "LBUS11") (class "Default")
      (node (ref "IC3") (pin "19") (pinfunction "A3_19") (pintype "input"))
      (node (ref "JP5") (pin "6") (pinfunction "6_6") (pintype "passive"))
    )
    (net (code "93") (name "LBUS12") (class "Default")
      (node (ref "IC4") (pin "2") (pinfunction "A0_2") (pintype "input"))
      (node (ref "JP5") (pin "3") (pinfunction "3_3") (pintype "passive"))
    )
    (net (code "94") (name "LBUS13") (class "Default")
      (node (ref "IC4") (pin "23") (pinfunction "A1_23") (pintype "input"))
      (node (ref "JP5") (pin "4") (pinfunction "4_4") (pintype "passive"))
    )
    (net (code "95") (name "LBUS14") (class "Default")
      (node (ref "IC4") (pin "21") (pinfunction "A2_21") (pintype "input"))
      (node (ref "JP5") (pin "1") (pinfunction "1_1") (pintype "passive"))
    )
    (net (code "96") (name "LBUS15") (class "Default")
      (node (ref "IC4") (pin "19") (pinfunction "A3_19") (pintype "input"))
      (node (ref "JP5") (pin "2") (pinfunction "2_2") (pintype "passive"))
    )
    (net (code "97") (name "LOAD_FLAGS0") (class "Default")
      (node (ref "JP9") (pin "24") (pinfunction "24_24") (pintype "passive"))
    )
    (net (code "98") (name "LOAD_FLAGS1") (class "Default")
      (node (ref "JP9") (pin "26") (pinfunction "26_26") (pintype "passive"))
    )
    (net (code "99") (name "MDRLDINHBT") (class "Default")
      (node (ref "JP9") (pin "43") (pinfunction "43_43") (pintype "passive"))
    )
    (net (code "100") (name "MEMSEG") (class "Default")
      (node (ref "JP10") (pin "14") (pinfunction "14_14") (pintype "passive"))
    )
    (net (code "101") (name "Net-(IC11A-G)") (class "Default")
      (node (ref "IC11") (pin "1") (pinfunction "G_1") (pintype "input"))
      (node (ref "IC12") (pin "1") (pinfunction "G_1") (pintype "input"))
      (node (ref "IC13") (pin "1") (pinfunction "G_1") (pintype "input"))
      (node (ref "IC14") (pin "1") (pinfunction "G_1") (pintype "input"))
      (node (ref "IC19") (pin "6") (pinfunction "O_6") (pintype "output"))
    )
    (net (code "102") (name "Net-(IC11B-G)") (class "Default")
      (node (ref "IC11") (pin "19") (pinfunction "G_19") (pintype "input"))
      (node (ref "IC12") (pin "19") (pinfunction "G_19") (pintype "input"))
      (node (ref "IC13") (pin "19") (pinfunction "G_19") (pintype "input"))
      (node (ref "IC14") (pin "19") (pinfunction "G_19") (pintype "input"))
      (node (ref "IC19") (pin "3") (pinfunction "O_3") (pintype "output"))
    )
    (net (code "103") (name "Net-(IC18C-O)") (class "Default")
      (node (ref "IC18") (pin "6") (pinfunction "O_6") (pintype "output"))
      (node (ref "IC19") (pin "2") (pinfunction "I1_2") (pintype "input"))
    )
    (net (code "104") (name "P0") (class "Default")
      (node (ref "IC1") (pin "15") (pinfunction "P_15") (pintype "output"))
      (node (ref "IC5") (pin "4") (pinfunction "P0_4") (pintype "input"))
    )
    (net (code "105") (name "P1") (class "Default")
      (node (ref "IC2") (pin "15") (pinfunction "P_15") (pintype "output"))
      (node (ref "IC5") (pin "2") (pinfunction "P1_2") (pintype "input"))
    )
    (net (code "106") (name "P2") (class "Default")
      (node (ref "IC3") (pin "15") (pinfunction "P_15") (pintype "output"))
      (node (ref "IC5") (pin "15") (pinfunction "P2_15") (pintype "input"))
    )
    (net (code "107") (name "P3") (class "Default")
      (node (ref "IC4") (pin "15") (pinfunction "P_15") (pintype "output"))
      (node (ref "IC5") (pin "6") (pinfunction "P3_6") (pintype "input"))
    )
    (net (code "108") (name "PROT") (class "Default")
      (node (ref "JP10") (pin "21") (pinfunction "21_21") (pintype "passive"))
    )
    (net (code "109") (name "RBUS0") (class "Default")
      (node (ref "IC1") (pin "1") (pinfunction "B0_1") (pintype "input"))
      (node (ref "JP4") (pin "1") (pinfunction "1_1") (pintype "passive"))
    )
    (net (code "110") (name "RBUS1") (class "Default")
      (node (ref "IC1") (pin "22") (pinfunction "B1_22") (pintype "input"))
      (node (ref "JP4") (pin "2") (pinfunction "2_2") (pintype "passive"))
    )
    (net (code "111") (name "RBUS2") (class "Default")
      (node (ref "IC1") (pin "20") (pinfunction "B2_20") (pintype "input"))
      (node (ref "JP4") (pin "3") (pinfunction "3_3") (pintype "passive"))
    )
    (net (code "112") (name "RBUS3") (class "Default")
      (node (ref "IC1") (pin "18") (pinfunction "B3_18") (pintype "input"))
      (node (ref "JP4") (pin "4") (pinfunction "4_4") (pintype "passive"))
    )
    (net (code "113") (name "RBUS4") (class "Default")
      (node (ref "IC2") (pin "1") (pinfunction "B0_1") (pintype "input"))
      (node (ref "JP4") (pin "5") (pinfunction "5_5") (pintype "passive"))
    )
    (net (code "114") (name "RBUS5") (class "Default")
      (node (ref "IC2") (pin "22") (pinfunction "B1_22") (pintype "input"))
      (node (ref "JP4") (pin "6") (pinfunction "6_6") (pintype "passive"))
    )
    (net (code "115") (name "RBUS6") (class "Default")
      (node (ref "IC2") (pin "20") (pinfunction "B2_20") (pintype "input"))
      (node (ref "JP4") (pin "7") (pinfunction "7_7") (pintype "passive"))
    )
    (net (code "116") (name "RBUS7") (class "Default")
      (node (ref "IC2") (pin "18") (pinfunction "B3_18") (pintype "input"))
      (node (ref "JP4") (pin "8") (pinfunction "8_8") (pintype "passive"))
    )
    (net (code "117") (name "RBUS8") (class "Default")
      (node (ref "IC3") (pin "1") (pinfunction "B0_1") (pintype "input"))
      (node (ref "JP4") (pin "9") (pinfunction "9_9") (pintype "passive"))
    )
    (net (code "118") (name "RBUS9") (class "Default")
      (node (ref "IC3") (pin "22") (pinfunction "B1_22") (pintype "input"))
      (node (ref "JP4") (pin "10") (pinfunction "10_10") (pintype "passive"))
    )
    (net (code "119") (name "RBUS10") (class "Default")
      (node (ref "IC3") (pin "20") (pinfunction "B2_20") (pintype "input"))
      (node (ref "JP4") (pin "11") (pinfunction "11_11") (pintype "passive"))
    )
    (net (code "120") (name "RBUS11") (class "Default")
      (node (ref "IC3") (pin "18") (pinfunction "B3_18") (pintype "input"))
      (node (ref "JP4") (pin "12") (pinfunction "12_12") (pintype "passive"))
    )
    (net (code "121") (name "RBUS12") (class "Default")
      (node (ref "IC4") (pin "1") (pinfunction "B0_1") (pintype "input"))
      (node (ref "JP4") (pin "13") (pinfunction "13_13") (pintype "passive"))
    )
    (net (code "122") (name "RBUS13") (class "Default")
      (node (ref "IC4") (pin "22") (pinfunction "B1_22") (pintype "input"))
      (node (ref "JP4") (pin "14") (pinfunction "14_14") (pintype "passive"))
    )
    (net (code "123") (name "RBUS14") (class "Default")
      (node (ref "IC4") (pin "20") (pinfunction "B2_20") (pintype "input"))
      (node (ref "JP4") (pin "15") (pinfunction "15_15") (pintype "passive"))
    )
    (net (code "124") (name "RBUS15") (class "Default")
      (node (ref "IC4") (pin "18") (pinfunction "B3_18") (pintype "input"))
      (node (ref "JP4") (pin "16") (pinfunction "16_16") (pintype "passive"))
    )
    (net (code "125") (name "RST") (class "Default")
      (node (ref "JP10") (pin "9") (pinfunction "9_9") (pintype "passive"))
    )
    (net (code "126") (name "SP_DIR") (class "Default")
      (node (ref "JP10") (pin "20") (pinfunction "20_20") (pintype "passive"))
    )
    (net (code "127") (name "unconnected-(IC1A-A=B-Pad14)") (class "Default")
      (node (ref "IC1") (pin "14") (pinfunction "A=B_14") (pintype "output"))
    )
    (net (code "128") (name "unconnected-(IC1A-CN+4-Pad16)") (class "Default")
      (node (ref "IC1") (pin "16") (pinfunction "CN+4_16") (pintype "output"))
    )
    (net (code "129") (name "unconnected-(IC2A-A=B-Pad14)") (class "Default")
      (node (ref "IC2") (pin "14") (pinfunction "A=B_14") (pintype "output"))
    )
    (net (code "130") (name "unconnected-(IC3A-A=B-Pad14)") (class "Default")
      (node (ref "IC3") (pin "14") (pinfunction "A=B_14") (pintype "output"))
    )
    (net (code "131") (name "unconnected-(IC3A-CN+4-Pad16)") (class "Default")
      (node (ref "IC3") (pin "16") (pinfunction "CN+4_16") (pintype "output"))
    )
    (net (code "132") (name "unconnected-(IC4A-A=B-Pad14)") (class "Default")
      (node (ref "IC4") (pin "14") (pinfunction "A=B_14") (pintype "output"))
    )
    (net (code "133") (name "unconnected-(IC5A-G-Pad10)") (class "Default")
      (node (ref "IC5") (pin "10") (pinfunction "G_10") (pintype "output"))
    )
    (net (code "134") (name "unconnected-(IC5A-P-Pad7)") (class "Default")
      (node (ref "IC5") (pin "7") (pinfunction "P_7") (pintype "output"))
    )
    (net (code "135") (name "unconnected-(IC18A-O-Pad2)") (class "Default")
      (node (ref "IC18") (pin "2") (pinfunction "O_2") (pintype "output"))
    )
    (net (code "136") (name "unconnected-(IC18B-O-Pad4)") (class "Default")
      (node (ref "IC18") (pin "4") (pinfunction "O_4") (pintype "output"))
    )
    (net (code "137") (name "unconnected-(IC18D-O-Pad8)") (class "Default")
      (node (ref "IC18") (pin "8") (pinfunction "O_8") (pintype "output"))
    )
    (net (code "138") (name "unconnected-(IC18E-O-Pad10)") (class "Default")
      (node (ref "IC18") (pin "10") (pinfunction "O_10") (pintype "output"))
    )
    (net (code "139") (name "unconnected-(IC18F-O-Pad12)") (class "Default")
      (node (ref "IC18") (pin "12") (pinfunction "O_12") (pintype "output"))
    )
    (net (code "140") (name "unconnected-(IC19C-O-Pad8)") (class "Default")
      (node (ref "IC19") (pin "8") (pinfunction "O_8") (pintype "output"))
    )
    (net (code "141") (name "unconnected-(IC19D-O-Pad11)") (class "Default")
      (node (ref "IC19") (pin "11") (pinfunction "O_11") (pintype "output"))
    )
    (net (code "142") (name "unconnected-(JP9-Pad15)") (class "Default")
      (node (ref "JP9") (pin "15") (pinfunction "15_15") (pintype "passive"))
    )
    (net (code "143") (name "unconnected-(JP9-Pad28)") (class "Default")
      (node (ref "JP9") (pin "28") (pinfunction "28_28") (pintype "passive"))
    )
    (net (code "144") (name "unconnected-(JP9-Pad30)") (class "Default")
      (node (ref "JP9") (pin "30") (pinfunction "30_30") (pintype "passive"))
    )
    (net (code "145") (name "unconnected-(JP9-Pad37)") (class "Default")
      (node (ref "JP9") (pin "37") (pinfunction "37_37") (pintype "passive"))
    )
    (net (code "146") (name "{slash}ALUCARRYIN") (class "Default")
      (node (ref "IC1") (pin "7") (pinfunction "CN_7") (pintype "input"))
      (node (ref "IC5") (pin "13") (pinfunction "CN_13") (pintype "input"))
      (node (ref "JP9") (pin "2") (pinfunction "2_2") (pintype "passive"))
    )
    (net (code "147") (name "{slash}ALUHI2MEM") (class "Default")
      (node (ref "JP10") (pin "25") (pinfunction "25_25") (pintype "passive"))
    )
    (net (code "148") (name "{slash}ALULO2MEM") (class "Default")
      (node (ref "JP10") (pin "29") (pinfunction "29_29") (pintype "passive"))
    )
    (net (code "149") (name "{slash}ALUSHR") (class "Default")
      (node (ref "IC18") (pin "5") (pinfunction "I_5") (pintype "input"))
      (node (ref "IC19") (pin "4") (pinfunction "I0_4") (pintype "input"))
      (node (ref "JP9") (pin "1") (pinfunction "1_1") (pintype "passive"))
    )
    (net (code "150") (name "{slash}BUSIFCEN") (class "Default")
      (node (ref "JP10") (pin "5") (pinfunction "5_5") (pintype "passive"))
    )
    (net (code "151") (name "{slash}CARRY1") (class "Default")
      (node (ref "IC2") (pin "16") (pinfunction "CN+4_16") (pintype "output"))
      (node (ref "JP9") (pin "29") (pinfunction "29_29") (pintype "passive"))
    )
    (net (code "152") (name "{slash}CARRY3") (class "Default")
      (node (ref "IC4") (pin "16") (pinfunction "CN+4_16") (pintype "output"))
      (node (ref "JP9") (pin "31") (pinfunction "31_31") (pintype "passive"))
    )
    (net (code "153") (name "{slash}CNTSP") (class "Default")
      (node (ref "JP10") (pin "3") (pinfunction "3_3") (pintype "passive"))
    )
    (net (code "154") (name "{slash}ENA") (class "Default")
      (node (ref "JP9") (pin "33") (pinfunction "33_33") (pintype "passive"))
    )
    (net (code "155") (name "{slash}ENABUS") (class "Default")
      (node (ref "JP10") (pin "22") (pinfunction "22_22") (pintype "passive"))
    )
    (net (code "156") (name "{slash}ENALU") (class "Default")
      (node (ref "IC19") (pin "1") (pinfunction "I0_1") (pintype "input"))
      (node (ref "IC19") (pin "5") (pinfunction "I1_5") (pintype "input"))
      (node (ref "JP9") (pin "39") (pinfunction "39_39") (pintype "passive"))
    )
    (net (code "157") (name "{slash}ENDP") (class "Default")
      (node (ref "JP9") (pin "44") (pinfunction "44_44") (pintype "passive"))
    )
    (net (code "158") (name "{slash}ENIPTR") (class "Default")
      (node (ref "JP9") (pin "38") (pinfunction "38_38") (pintype "passive"))
    )
    (net (code "159") (name "{slash}ENLMDR") (class "Default")
      (node (ref "JP9") (pin "34") (pinfunction "34_34") (pintype "passive"))
    )
    (net (code "160") (name "{slash}ENMAR") (class "Default")
      (node (ref "JP9") (pin "48") (pinfunction "48_48") (pintype "passive"))
    )
    (net (code "161") (name "{slash}ENMEM") (class "Default")
      (node (ref "JP10") (pin "16") (pinfunction "16_16") (pintype "passive"))
    )
    (net (code "162") (name "{slash}ENMSW") (class "Default")
      (node (ref "JP9") (pin "40") (pinfunction "40_40") (pintype "passive"))
    )
    (net (code "163") (name "{slash}ENPC") (class "Default")
      (node (ref "JP9") (pin "42") (pinfunction "42_42") (pintype "passive"))
    )
    (net (code "164") (name "{slash}ENRMDR") (class "Default")
      (node (ref "JP9") (pin "41") (pinfunction "41_41") (pintype "passive"))
    )
    (net (code "165") (name "{slash}ENSP") (class "Default")
      (node (ref "JP9") (pin "46") (pinfunction "46_46") (pintype "passive"))
    )
    (net (code "166") (name "{slash}ENX") (class "Default")
      (node (ref "JP9") (pin "36") (pinfunction "36_36") (pintype "passive"))
    )
    (net (code "167") (name "{slash}ENY") (class "Default")
      (node (ref "JP9") (pin "35") (pinfunction "35_35") (pintype "passive"))
    )
    (net (code "168") (name "{slash}FI") (class "Default")
      (node (ref "JP10") (pin "32") (pinfunction "32_32") (pintype "passive"))
    )
    (net (code "169") (name "{slash}FP") (class "Default")
      (node (ref "JP10") (pin "34") (pinfunction "34_34") (pintype "passive"))
    )
    (net (code "170") (name "{slash}FS") (class "Default")
      (node (ref "JP10") (pin "30") (pinfunction "30_30") (pintype "passive"))
    )
    (net (code "171") (name "{slash}INCPC") (class "Default")
      (node (ref "JP10") (pin "1") (pinfunction "1_1") (pintype "passive"))
    )
    (net (code "172") (name "{slash}INC_MAR") (class "Default")
      (node (ref "JP9") (pin "32") (pinfunction "32_32") (pintype "passive"))
    )
    (net (code "173") (name "{slash}IO") (class "Default")
      (node (ref "JP10") (pin "35") (pinfunction "35_35") (pintype "passive"))
    )
    (net (code "174") (name "{slash}LATCHFLAGS") (class "Default")
      (node (ref "JP10") (pin "12") (pinfunction "12_12") (pintype "passive"))
    )
    (net (code "175") (name "{slash}LATCH_I") (class "Default")
      (node (ref "JP9") (pin "47") (pinfunction "47_47") (pintype "passive"))
    )
    (net (code "176") (name "{slash}LATCH_S") (class "Default")
      (node (ref "JP9") (pin "45") (pinfunction "45_45") (pintype "passive"))
    )
    (net (code "177") (name "{slash}LDA") (class "Default")
      (node (ref "JP9") (pin "14") (pinfunction "14_14") (pintype "passive"))
    )
    (net (code "178") (name "{slash}LDAHI") (class "Default")
      (node (ref "JP9") (pin "11") (pinfunction "11_11") (pintype "passive"))
    )
    (net (code "179") (name "{slash}LDALO") (class "Default")
      (node (ref "JP9") (pin "12") (pinfunction "12_12") (pintype "passive"))
    )
    (net (code "180") (name "{slash}LDDP") (class "Default")
      (node (ref "JP9") (pin "22") (pinfunction "22_22") (pintype "passive"))
    )
    (net (code "181") (name "{slash}LDMAR") (class "Default")
      (node (ref "JP9") (pin "23") (pinfunction "23_23") (pintype "passive"))
    )
    (net (code "182") (name "{slash}LDMARHI") (class "Default")
      (node (ref "JP9") (pin "17") (pinfunction "17_17") (pintype "passive"))
    )
    (net (code "183") (name "{slash}LDMARLO") (class "Default")
      (node (ref "JP9") (pin "18") (pinfunction "18_18") (pintype "passive"))
    )
    (net (code "184") (name "{slash}LDMDR") (class "Default")
      (node (ref "JP9") (pin "9") (pinfunction "9_9") (pintype "passive"))
    )
    (net (code "185") (name "{slash}LDMDRHI") (class "Default")
      (node (ref "JP9") (pin "10") (pinfunction "10_10") (pintype "passive"))
    )
    (net (code "186") (name "{slash}LDMDRLO") (class "Default")
      (node (ref "JP9") (pin "7") (pinfunction "7_7") (pintype "passive"))
    )
    (net (code "187") (name "{slash}LDMEM") (class "Default")
      (node (ref "JP10") (pin "15") (pinfunction "15_15") (pintype "passive"))
    )
    (net (code "188") (name "{slash}LDMSW") (class "Default")
      (node (ref "JP9") (pin "20") (pinfunction "20_20") (pintype "passive"))
    )
    (net (code "189") (name "{slash}LDPC") (class "Default")
      (node (ref "JP9") (pin "19") (pinfunction "19_19") (pintype "passive"))
    )
    (net (code "190") (name "{slash}LDSP") (class "Default")
      (node (ref "JP9") (pin "21") (pinfunction "21_21") (pintype "passive"))
    )
    (net (code "191") (name "{slash}LDX") (class "Default")
      (node (ref "JP9") (pin "13") (pinfunction "13_13") (pintype "passive"))
    )
    (net (code "192") (name "{slash}LDY") (class "Default")
      (node (ref "JP9") (pin "16") (pinfunction "16_16") (pintype "passive"))
    )
    (net (code "193") (name "{slash}LOAD_IR") (class "Default")
      (node (ref "JP10") (pin "26") (pinfunction "26_26") (pintype "passive"))
    )
    (net (code "194") (name "{slash}MEM2ALUHI") (class "Default")
      (node (ref "JP10") (pin "27") (pinfunction "27_27") (pintype "passive"))
    )
    (net (code "195") (name "{slash}MEM2ALULO") (class "Default")
      (node (ref "JP10") (pin "31") (pinfunction "31_31") (pintype "passive"))
    )
    (net (code "196") (name "{slash}MEMOP") (class "Default")
      (node (ref "JP10") (pin "11") (pinfunction "11_11") (pintype "passive"))
    )
    (net (code "197") (name "{slash}NP_FAULT") (class "Default")
      (node (ref "JP10") (pin "36") (pinfunction "36_36") (pintype "passive"))
    )
    (net (code "198") (name "{slash}RST") (class "Default")
      (node (ref "JP10") (pin "7") (pinfunction "7_7") (pintype "passive"))
    )
    (net (code "199") (name "{slash}WR_FAULT") (class "Default")
      (node (ref "JP10") (pin "33") (pinfunction "33_33") (pintype "passive"))
    )
  )
)
